# USBprotector.net
KiCad netlist of a schematic drawn in EAGLE
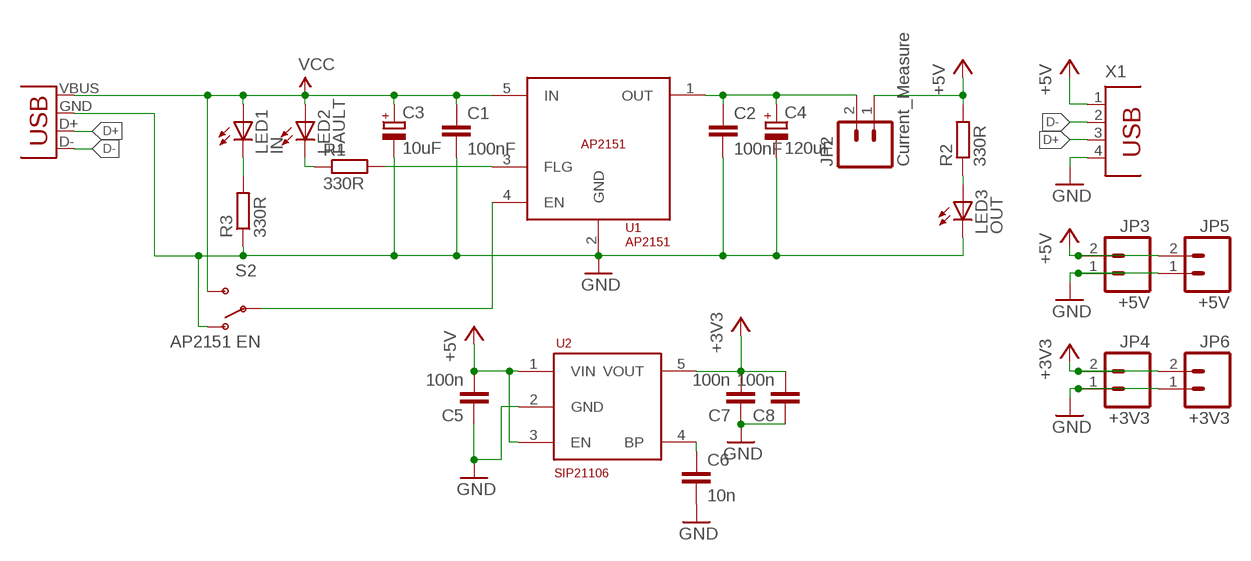
[diagram p0: schematic, sheet 1]

(export (version "E")
  (design (tool "Eeschema 10.0.6"))
  (components
    (comp (ref "C1")
      (value "100nF")
      (footprint "eagle-import:C0805")
      (libsource (lib "eagle-import") (part "C-EUC0805"))
    )
    (comp (ref "C2")
      (value "100nF")
      (footprint "eagle-import:C0805")
      (libsource (lib "eagle-import") (part "C-EUC0805"))
    )
    (comp (ref "C3")
      (value "10uF")
      (footprint "eagle-import:SMC_C")
      (libsource (lib "eagle-import") (part "CPOL-EUSMCC"))
    )
    (comp (ref "C4")
      (value "120uF")
      (footprint "eagle-import:SMC_C")
      (libsource (lib "eagle-import") (part "CPOL-EUSMCC"))
    )
    (comp (ref "C5")
      (value "100n")
      (footprint "eagle-import:C0805")
      (libsource (lib "eagle-import") (part "C-EUC0805"))
    )
    (comp (ref "C6")
      (value "10n")
      (footprint "eagle-import:C0805")
      (libsource (lib "eagle-import") (part "C-EUC0805"))
    )
    (comp (ref "C7")
      (value "100n")
      (footprint "eagle-import:C0603")
      (libsource (lib "eagle-import") (part "C-EUC0603"))
    )
    (comp (ref "C8")
      (value "100n")
      (footprint "eagle-import:C0805")
      (libsource (lib "eagle-import") (part "C-EUC0805"))
    )
    (comp (ref "JP1")
      (value "USB-A-H")
      (footprint "eagle-import:USB-A-H")
      (libsource (lib "eagle-import") (part "USB-A-H"))
    )
    (comp (ref "JP2")
      (value "Current_Measure")
      (footprint "eagle-import:1X02")
      (libsource (lib "eagle-import") (part "M02PTH"))
    )
    (comp (ref "JP3")
      (value "+5V")
      (footprint "eagle-import:SCREWTERMINAL-3.5MM-2")
      (libsource (lib "eagle-import") (part "M023.5MM"))
    )
    (comp (ref "JP4")
      (value "+3V3")
      (footprint "eagle-import:SCREWTERMINAL-3.5MM-2")
      (libsource (lib "eagle-import") (part "M023.5MM"))
    )
    (comp (ref "JP5")
      (value "+5V")
      (footprint "eagle-import:MOLEX-1X2_LOCK")
      (libsource (lib "eagle-import") (part "M02POLAR_LOCK"))
    )
    (comp (ref "JP6")
      (value "+3V3")
      (footprint "eagle-import:MOLEX-1X2_LOCK")
      (libsource (lib "eagle-import") (part "M02POLAR_LOCK"))
    )
    (comp (ref "LED1")
      (value "IN")
      (footprint "eagle-import:LED3MM")
      (libsource (lib "eagle-import") (part "LED3MM"))
    )
    (comp (ref "LED2")
      (value "FAULT")
      (footprint "eagle-import:LED3MM")
      (libsource (lib "eagle-import") (part "LED3MM"))
    )
    (comp (ref "LED3")
      (value "OUT")
      (footprint "eagle-import:LED3MM")
      (libsource (lib "eagle-import") (part "LED3MM"))
    )
    (comp (ref "R1")
      (value "330R")
      (footprint "eagle-import:R1206")
      (libsource (lib "eagle-import") (part "R-EU_R1206"))
    )
    (comp (ref "R2")
      (value "330R")
      (footprint "eagle-import:R1206")
      (libsource (lib "eagle-import") (part "R-EU_R1206"))
    )
    (comp (ref "R3")
      (value "330R")
      (footprint "eagle-import:R1206")
      (libsource (lib "eagle-import") (part "R-EU_R1206"))
    )
    (comp (ref "S2")
      (value "AP2151 EN")
      (footprint "eagle-import:SWITCH-SPDT")
      (libsource (lib "eagle-import") (part "SWITCH-SPDTPTH"))
    )
    (comp (ref "U1")
      (value "AP2151")
      (footprint "eagle-import:SOT23-5")
      (libsource (lib "eagle-import") (part "AP2151"))
    )
    (comp (ref "U2")
      (value "SIP21106")
      (footprint "eagle-import:SOT23-5")
      (libsource (lib "eagle-import") (part "SIP21106"))
    )
    (comp (ref "X1")
      (value "PN87520")
      (footprint "eagle-import:PN87520")
      (libsource (lib "eagle-import") (part "PN87520"))
    )
  )
  (nets
    (net (code "1") (name "+3V3") (class "Default")
      (node (ref "C7") (pin "2") (pinfunction "2_2") (pintype "passive"))
      (node (ref "C8") (pin "2") (pinfunction "2_2") (pintype "passive"))
      (node (ref "JP4") (pin "2") (pinfunction "2_2") (pintype "passive"))
      (node (ref "JP6") (pin "2") (pinfunction "2_2") (pintype "passive"))
      (node (ref "U2") (pin "5") (pinfunction "VOUT_5") (pintype "bidirectional"))
    )
    (net (code "2") (name "+5V") (class "Default")
      (node (ref "C5") (pin "2") (pinfunction "2_2") (pintype "passive"))
      (node (ref "JP2") (pin "1") (pinfunction "1_1") (pintype "passive"))
      (node (ref "JP3") (pin "2") (pinfunction "2_2") (pintype "passive"))
      (node (ref "JP5") (pin "2") (pinfunction "2_2") (pintype "passive"))
      (node (ref "R2") (pin "2") (pinfunction "2_2") (pintype "passive"))
      (node (ref "U2") (pin "1") (pinfunction "VIN_1") (pintype "bidirectional"))
      (node (ref "U2") (pin "3") (pinfunction "EN_3") (pintype "bidirectional"))
      (node (ref "X1") (pin "1") (pinfunction "1_1") (pintype "passive"))
    )
    (net (code "3") (name "D+") (class "Default")
      (node (ref "JP1") (pin "D+") (pinfunction "D-_D+") (pintype "bidirectional"))
      (node (ref "X1") (pin "3") (pinfunction "3_3") (pintype "passive"))
    )
    (net (code "4") (name "D-") (class "Default")
      (node (ref "JP1") (pin "D-") (pinfunction "D+_D-") (pintype "bidirectional"))
      (node (ref "X1") (pin "2") (pinfunction "2_2") (pintype "passive"))
    )
    (net (code "5") (name "GND") (class "Default")
      (node (ref "C1") (pin "2") (pinfunction "2_2") (pintype "passive"))
      (node (ref "C2") (pin "2") (pinfunction "2_2") (pintype "passive"))
      (node (ref "C3") (pin "-") (pinfunction "-_-") (pintype "passive"))
      (node (ref "C4") (pin "-") (pinfunction "-_-") (pintype "passive"))
      (node (ref "C5") (pin "1") (pinfunction "1_1") (pintype "passive"))
      (node (ref "C6") (pin "2") (pinfunction "2_2") (pintype "passive"))
      (node (ref "C7") (pin "1") (pinfunction "1_1") (pintype "passive"))
      (node (ref "C8") (pin "1") (pinfunction "1_1") (pintype "passive"))
      (node (ref "JP1") (pin "GND") (pinfunction "VBUS_GND") (pintype "bidirectional"))
      (node (ref "JP3") (pin "1") (pinfunction "1_1") (pintype "passive"))
      (node (ref "JP4") (pin "1") (pinfunction "1_1") (pintype "passive"))
      (node (ref "JP5") (pin "1") (pinfunction "1_1") (pintype "passive"))
      (node (ref "JP6") (pin "1") (pinfunction "1_1") (pintype "passive"))
      (node (ref "LED3") (pin "K") (pinfunction "C_K") (pintype "passive"))
      (node (ref "R3") (pin "1") (pinfunction "1_1") (pintype "passive"))
      (node (ref "S2") (pin "1") (pinfunction "O_1") (pintype "passive"))
      (node (ref "U1") (pin "2") (pinfunction "GND_2") (pintype "power_in"))
      (node (ref "U2") (pin "2") (pinfunction "GND_2") (pintype "bidirectional"))
      (node (ref "X1") (pin "4") (pinfunction "4_4") (pintype "passive"))
    )
    (net (code "6") (name "Net-(LED1-C)") (class "Default")
      (node (ref "LED1") (pin "K") (pinfunction "C_K") (pintype "passive"))
      (node (ref "R3") (pin "2") (pinfunction "2_2") (pintype "passive"))
    )
    (net (code "7") (name "Net-(LED2-C)") (class "Default")
      (node (ref "LED2") (pin "K") (pinfunction "C_K") (pintype "passive"))
      (node (ref "R1") (pin "1") (pinfunction "1_1") (pintype "passive"))
    )
    (net (code "8") (name "Net-(LED3-PadA)") (class "Default")
      (node (ref "LED3") (pin "A") (pinfunction "A_A") (pintype "passive"))
      (node (ref "R2") (pin "1") (pinfunction "1_1") (pintype "passive"))
    )
    (net (code "9") (name "Net-(S2-P)") (class "Default")
      (node (ref "S2") (pin "2") (pinfunction "P_2") (pintype "passive"))
      (node (ref "U1") (pin "4") (pinfunction "EN_4") (pintype "bidirectional"))
    )
    (net (code "10") (name "Net-(U1-FLG)") (class "Default")
      (node (ref "R1") (pin "2") (pinfunction "2_2") (pintype "passive"))
      (node (ref "U1") (pin "3") (pinfunction "FLG_3") (pintype "bidirectional"))
    )
    (net (code "11") (name "Net-(U1-OUT)") (class "Default")
      (node (ref "C2") (pin "1") (pinfunction "1_1") (pintype "passive"))
      (node (ref "C4") (pin "+") (pinfunction "+_+") (pintype "passive"))
      (node (ref "JP2") (pin "2") (pinfunction "2_2") (pintype "passive"))
      (node (ref "U1") (pin "1") (pinfunction "OUT_1") (pintype "power_in"))
    )
    (net (code "12") (name "Net-(U2-BP)") (class "Default")
      (node (ref "C6") (pin "1") (pinfunction "1_1") (pintype "passive"))
      (node (ref "U2") (pin "4") (pinfunction "BP_4") (pintype "bidirectional"))
    )
    (net (code "13") (name "VCC") (class "Default")
      (node (ref "C1") (pin "1") (pinfunction "1_1") (pintype "passive"))
      (node (ref "C3") (pin "+") (pinfunction "+_+") (pintype "passive"))
      (node (ref "JP1") (pin "VBUS") (pinfunction "GND_VBUS") (pintype "bidirectional"))
      (node (ref "LED1") (pin "A") (pinfunction "A_A") (pintype "passive"))
      (node (ref "LED2") (pin "A") (pinfunction "A_A") (pintype "passive"))
      (node (ref "S2") (pin "3") (pinfunction "S_3") (pintype "passive"))
      (node (ref "U1") (pin "5") (pinfunction "IN_5") (pintype "power_in"))
    )
  )
)
